# UART_LOGIC.net
KiCad netlist of a schematic drawn in Altium Designer
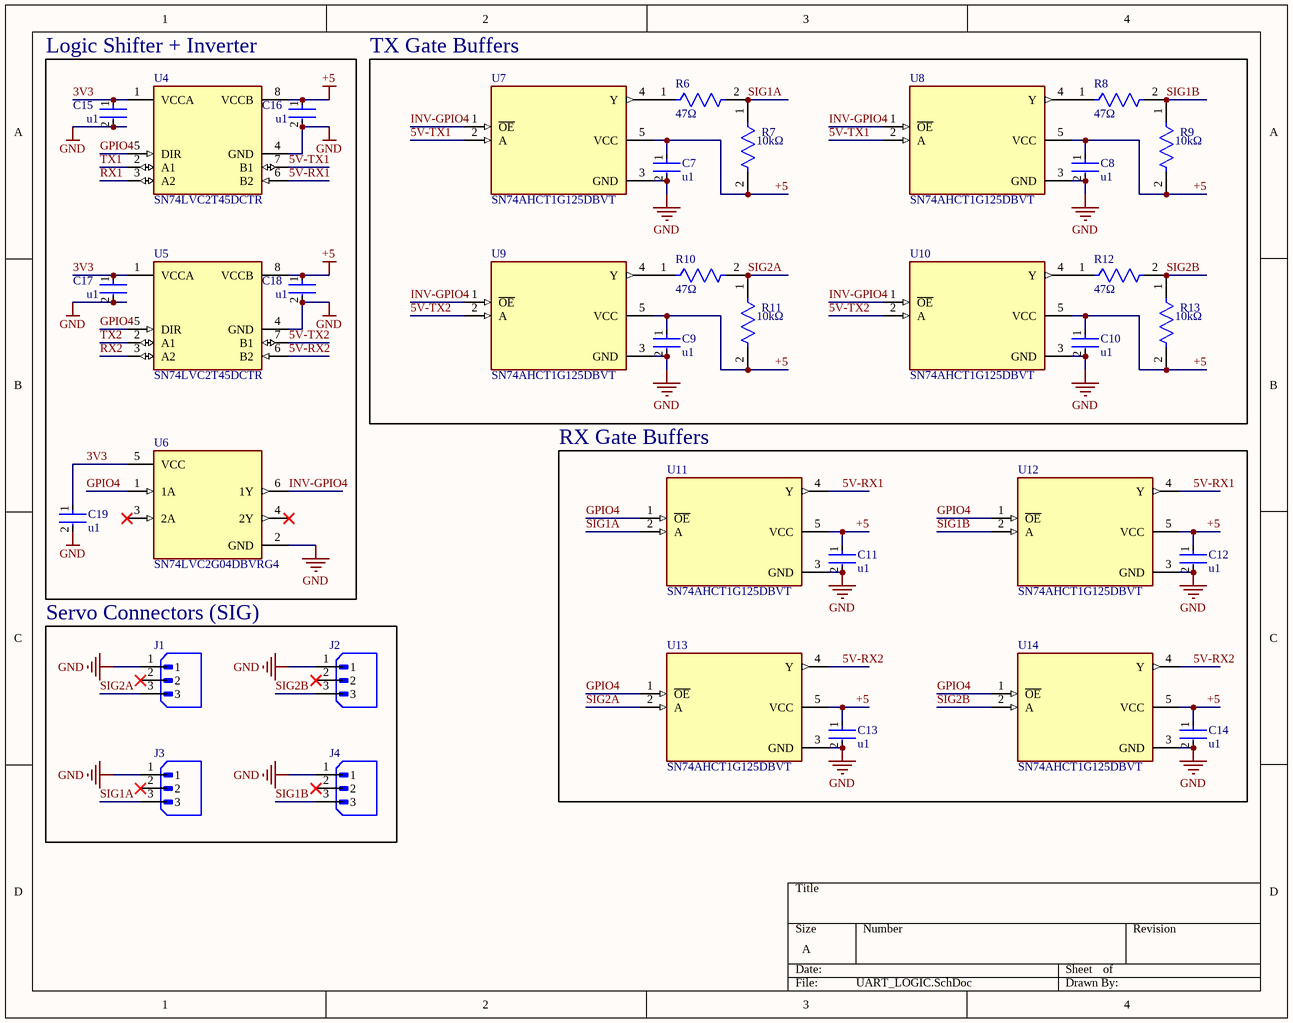
[diagram p0: UART_LOGIC.SchDoc]

(export (version "E")
  (design (tool "Eeschema 10.0.6"))
  (components
    (comp (ref "C7")
      (value "u1")
      (footprint "FP-CC0805-0_85-MFG")
      (description "CC0805KRX7R9BB104 CAP CER 0.1UF 50V X7R 0805")
      (fields (field (name "TOLERANCE") "0.1") (field (name "MANUFACTURER PART NUMBER") "CC0805KRX7R9BB104"))
      (libsource (lib "Altium Content Vault") (part "11868f565c42a9108669ba33697ecf6"))
    )
    (comp (ref "C8")
      (value "u1")
      (footprint "FP-CC0805-0_85-MFG")
      (description "CC0805KRX7R9BB104 CAP CER 0.1UF 50V X7R 0805")
      (fields (field (name "TOLERANCE") "0.1") (field (name "MANUFACTURER PART NUMBER") "CC0805KRX7R9BB104"))
      (libsource (lib "Altium Content Vault") (part "11868f565c42a9108669ba33697ecf6"))
    )
    (comp (ref "C9")
      (value "u1")
      (footprint "FP-CC0805-0_85-MFG")
      (description "CC0805KRX7R9BB104 CAP CER 0.1UF 50V X7R 0805")
      (fields (field (name "TOLERANCE") "0.1") (field (name "MANUFACTURER PART NUMBER") "CC0805KRX7R9BB104"))
      (libsource (lib "Altium Content Vault") (part "11868f565c42a9108669ba33697ecf6"))
    )
    (comp (ref "C10")
      (value "u1")
      (footprint "FP-CC0805-0_85-MFG")
      (description "CC0805KRX7R9BB104 CAP CER 0.1UF 50V X7R 0805")
      (fields (field (name "TOLERANCE") "0.1") (field (name "MANUFACTURER PART NUMBER") "CC0805KRX7R9BB104"))
      (libsource (lib "Altium Content Vault") (part "11868f565c42a9108669ba33697ecf6"))
    )
    (comp (ref "C11")
      (value "u1")
      (footprint "FP-CC0805-0_85-MFG")
      (description "CC0805KRX7R9BB104 CAP CER 0.1UF 50V X7R 0805")
      (fields (field (name "TOLERANCE") "0.1") (field (name "MANUFACTURER PART NUMBER") "CC0805KRX7R9BB104"))
      (libsource (lib "Altium Content Vault") (part "11868f565c42a9108669ba33697ecf6"))
    )
    (comp (ref "C12")
      (value "u1")
      (footprint "FP-CC0805-0_85-MFG")
      (description "CC0805KRX7R9BB104 CAP CER 0.1UF 50V X7R 0805")
      (fields (field (name "TOLERANCE") "0.1") (field (name "MANUFACTURER PART NUMBER") "CC0805KRX7R9BB104"))
      (libsource (lib "Altium Content Vault") (part "11868f565c42a9108669ba33697ecf6"))
    )
    (comp (ref "C13")
      (value "u1")
      (footprint "FP-CC0805-0_85-MFG")
      (description "CC0805KRX7R9BB104 CAP CER 0.1UF 50V X7R 0805")
      (fields (field (name "TOLERANCE") "0.1") (field (name "MANUFACTURER PART NUMBER") "CC0805KRX7R9BB104"))
      (libsource (lib "Altium Content Vault") (part "11868f565c42a9108669ba33697ecf6"))
    )
    (comp (ref "C14")
      (value "u1")
      (footprint "FP-CC0805-0_85-MFG")
      (description "CC0805KRX7R9BB104 CAP CER 0.1UF 50V X7R 0805")
      (fields (field (name "TOLERANCE") "0.1") (field (name "MANUFACTURER PART NUMBER") "CC0805KRX7R9BB104"))
      (libsource (lib "Altium Content Vault") (part "11868f565c42a9108669ba33697ecf6"))
    )
    (comp (ref "C15")
      (value "u1")
      (footprint "FP-CC0805-0_85-MFG")
      (description "CC0805KRX7R9BB104 CAP CER 0.1UF 50V X7R 0805")
      (fields (field (name "TOLERANCE") "0.1") (field (name "MANUFACTURER PART NUMBER") "CC0805KRX7R9BB104"))
      (libsource (lib "Altium Content Vault") (part "11868f565c42a9108669ba33697ecf6"))
    )
    (comp (ref "C16")
      (value "u1")
      (footprint "FP-CC0805-0_85-MFG")
      (description "CC0805KRX7R9BB104 CAP CER 0.1UF 50V X7R 0805")
      (fields (field (name "TOLERANCE") "0.1") (field (name "MANUFACTURER PART NUMBER") "CC0805KRX7R9BB104"))
      (libsource (lib "Altium Content Vault") (part "11868f565c42a9108669ba33697ecf6"))
    )
    (comp (ref "C17")
      (value "u1")
      (footprint "FP-CC0805-0_85-MFG")
      (description "CC0805KRX7R9BB104 CAP CER 0.1UF 50V X7R 0805")
      (fields (field (name "TOLERANCE") "0.1") (field (name "MANUFACTURER PART NUMBER") "CC0805KRX7R9BB104"))
      (libsource (lib "Altium Content Vault") (part "11868f565c42a9108669ba33697ecf6"))
    )
    (comp (ref "C18")
      (value "u1")
      (footprint "FP-CC0805-0_85-MFG")
      (description "CC0805KRX7R9BB104 CAP CER 0.1UF 50V X7R 0805")
      (fields (field (name "TOLERANCE") "0.1") (field (name "MANUFACTURER PART NUMBER") "CC0805KRX7R9BB104"))
      (libsource (lib "Altium Content Vault") (part "11868f565c42a9108669ba33697ecf6"))
    )
    (comp (ref "C19")
      (value "u1")
      (footprint "FP-CC0805-0_85-MFG")
      (description "CC0805KRX7R9BB104 CAP CER 0.1UF 50V X7R 0805")
      (fields (field (name "TOLERANCE") "0.1") (field (name "MANUFACTURER PART NUMBER") "CC0805KRX7R9BB104"))
      (libsource (lib "Altium Content Vault") (part "11868f565c42a9108669ba33697ecf6"))
    )
    (comp (ref "J1")
      (value "B3B-XH-A")
      (footprint "JST_B3B-XH-A")
      (description "Connector Header Through Hole 3 position 0.098 (2.50mm)")
      (fields (field (name "MF") "JST Sales"))
      (libsource (lib "Bryan Heddle") (part "B3B-XH-A"))
    )
    (comp (ref "J2")
      (value "B3B-XH-A")
      (footprint "JST_B3B-XH-A")
      (description "Connector Header Through Hole 3 position 0.098 (2.50mm)")
      (fields (field (name "MF") "JST Sales"))
      (libsource (lib "Bryan Heddle") (part "B3B-XH-A"))
    )
    (comp (ref "J3")
      (value "B3B-XH-A")
      (footprint "JST_B3B-XH-A")
      (description "Connector Header Through Hole 3 position 0.098 (2.50mm)")
      (fields (field (name "MF") "JST Sales"))
      (libsource (lib "Bryan Heddle") (part "B3B-XH-A"))
    )
    (comp (ref "J4")
      (value "B3B-XH-A")
      (footprint "JST_B3B-XH-A")
      (description "Connector Header Through Hole 3 position 0.098 (2.50mm)")
      (fields (field (name "MF") "JST Sales"))
      (libsource (lib "Bryan Heddle") (part "B3B-XH-A"))
    )
    (comp (ref "R6")
      (value "47Ω")
      (footprint "FP-RMCF0603-IPC_A")
      (description "47Ω ±1% 0.1W 0603 Thick Film Chip Resistor AEC-Q200 compliant RMCF0603FG47R0")
      (libsource (lib "Altium Content Vault") (part "1029c3af85768c4190bb7ad29bc67b5"))
    )
    (comp (ref "R7")
      (value "10kΩ")
      (footprint "FP-RMCF1206-MFG")
      (description "10kΩ ±1% 0.25W 1206 Thick Film Chip Resistor AEC-Q200 compliant RMCF1206FG10K0")
      (fields (field (name "TOLERANCE") "1%"))
      (libsource (lib "Altium Content Vault") (part "1029c3af85768c4190bb7ad29bc67b5"))
    )
    (comp (ref "R8")
      (value "47Ω")
      (footprint "FP-RMCF0603-IPC_A")
      (description "47Ω ±1% 0.1W 0603 Thick Film Chip Resistor AEC-Q200 compliant RMCF0603FG47R0")
      (libsource (lib "Altium Content Vault") (part "1029c3af85768c4190bb7ad29bc67b5"))
    )
    (comp (ref "R9")
      (value "10kΩ")
      (footprint "FP-RMCF1206-MFG")
      (description "10kΩ ±1% 0.25W 1206 Thick Film Chip Resistor AEC-Q200 compliant RMCF1206FG10K0")
      (fields (field (name "TOLERANCE") "1%"))
      (libsource (lib "Altium Content Vault") (part "1029c3af85768c4190bb7ad29bc67b5"))
    )
    (comp (ref "R10")
      (value "47Ω")
      (footprint "FP-RMCF0603-IPC_A")
      (description "47Ω ±1% 0.1W 0603 Thick Film Chip Resistor AEC-Q200 compliant RMCF0603FG47R0")
      (libsource (lib "Altium Content Vault") (part "1029c3af85768c4190bb7ad29bc67b5"))
    )
    (comp (ref "R11")
      (value "10kΩ")
      (footprint "FP-RMCF1206-MFG")
      (description "10kΩ ±1% 0.25W 1206 Thick Film Chip Resistor AEC-Q200 compliant RMCF1206FG10K0")
      (fields (field (name "TOLERANCE") "1%"))
      (libsource (lib "Altium Content Vault") (part "1029c3af85768c4190bb7ad29bc67b5"))
    )
    (comp (ref "R12")
      (value "47Ω")
      (footprint "FP-RMCF0603-IPC_A")
      (description "47Ω ±1% 0.1W 0603 Thick Film Chip Resistor AEC-Q200 compliant RMCF0603FG47R0")
      (libsource (lib "Altium Content Vault") (part "1029c3af85768c4190bb7ad29bc67b5"))
    )
    (comp (ref "R13")
      (value "10kΩ")
      (footprint "FP-RMCF1206-MFG")
      (description "10kΩ ±1% 0.25W 1206 Thick Film Chip Resistor AEC-Q200 compliant RMCF1206FG10K0")
      (fields (field (name "TOLERANCE") "1%"))
      (libsource (lib "Altium Content Vault") (part "1029c3af85768c4190bb7ad29bc67b5"))
    )
    (comp (ref "U4")
      (value "SN74LVC2T45DCTR")
      (footprint "FP-DCT0008A-IPC_C")
      (libsource (lib "Bryan Heddle") (part "271d40e9c72c712db4b2912206096bb"))
    )
    (comp (ref "U5")
      (value "SN74LVC2T45DCTR")
      (footprint "FP-DCT0008A-IPC_C")
      (libsource (lib "Bryan Heddle") (part "271d40e9c72c712db4b2912206096bb"))
    )
    (comp (ref "U6")
      (value "SN74LVC2G04DBVRG4")
      (footprint "FP-DBV0006A-MFG")
      (description "IC INVERTER 2CH 2-INP SOT23-6")
      (libsource (lib "Altium Content Vault") (part "9dfbf26b1eab2647ff4a890ff2a17ee"))
    )
    (comp (ref "U7")
      (value "SN74AHCT1G125DBVT")
      (footprint "SOT95P280X145-5N")
      (description "Single 4.5-V to 5.5-V buffer with TTL-compatible CMOS inputs and 3-state outputs")
      (fields (field (name "MF") "Texas Instruments"))
      (libsource (lib "Bryan Heddle") (part "SN74AHCT1G125DBVT"))
    )
    (comp (ref "U8")
      (value "SN74AHCT1G125DBVT")
      (footprint "SOT95P280X145-5N")
      (description "Single 4.5-V to 5.5-V buffer with TTL-compatible CMOS inputs and 3-state outputs")
      (fields (field (name "MF") "Texas Instruments"))
      (libsource (lib "Bryan Heddle") (part "SN74AHCT1G125DBVT"))
    )
    (comp (ref "U9")
      (value "SN74AHCT1G125DBVT")
      (footprint "SOT95P280X145-5N")
      (description "Single 4.5-V to 5.5-V buffer with TTL-compatible CMOS inputs and 3-state outputs")
      (fields (field (name "MF") "Texas Instruments"))
      (libsource (lib "Bryan Heddle") (part "SN74AHCT1G125DBVT"))
    )
    (comp (ref "U10")
      (value "SN74AHCT1G125DBVT")
      (footprint "SOT95P280X145-5N")
      (description "Single 4.5-V to 5.5-V buffer with TTL-compatible CMOS inputs and 3-state outputs")
      (fields (field (name "MF") "Texas Instruments"))
      (libsource (lib "Bryan Heddle") (part "SN74AHCT1G125DBVT"))
    )
    (comp (ref "U11")
      (value "SN74AHCT1G125DBVT")
      (footprint "SOT95P280X145-5N")
      (description "Single 4.5-V to 5.5-V buffer with TTL-compatible CMOS inputs and 3-state outputs")
      (fields (field (name "MF") "Texas Instruments"))
      (libsource (lib "Bryan Heddle") (part "SN74AHCT1G125DBVT"))
    )
    (comp (ref "U12")
      (value "SN74AHCT1G125DBVT")
      (footprint "SOT95P280X145-5N")
      (description "Single 4.5-V to 5.5-V buffer with TTL-compatible CMOS inputs and 3-state outputs")
      (fields (field (name "MF") "Texas Instruments"))
      (libsource (lib "Bryan Heddle") (part "SN74AHCT1G125DBVT"))
    )
    (comp (ref "U13")
      (value "SN74AHCT1G125DBVT")
      (footprint "SOT95P280X145-5N")
      (description "Single 4.5-V to 5.5-V buffer with TTL-compatible CMOS inputs and 3-state outputs")
      (fields (field (name "MF") "Texas Instruments"))
      (libsource (lib "Bryan Heddle") (part "SN74AHCT1G125DBVT"))
    )
    (comp (ref "U14")
      (value "SN74AHCT1G125DBVT")
      (footprint "SOT95P280X145-5N")
      (description "Single 4.5-V to 5.5-V buffer with TTL-compatible CMOS inputs and 3-state outputs")
      (fields (field (name "MF") "Texas Instruments"))
      (libsource (lib "Bryan Heddle") (part "SN74AHCT1G125DBVT"))
    )
  )
  (nets
    (net (code "1") (name "+5") (class "Default")
      (node (ref "C10") (pin "1") (pinfunction "1_1") (pintype "passive"))
      (node (ref "C11") (pin "1") (pinfunction "1_1") (pintype "passive"))
      (node (ref "C12") (pin "1") (pinfunction "1_1") (pintype "passive"))
      (node (ref "C13") (pin "1") (pinfunction "1_1") (pintype "passive"))
      (node (ref "C14") (pin "1") (pinfunction "1_1") (pintype "passive"))
      (node (ref "C16") (pin "1") (pinfunction "1_1") (pintype "passive"))
      (node (ref "C18") (pin "1") (pinfunction "1_1") (pintype "passive"))
      (node (ref "C7") (pin "1") (pinfunction "1_1") (pintype "passive"))
      (node (ref "C8") (pin "1") (pinfunction "1_1") (pintype "passive"))
      (node (ref "C9") (pin "1") (pinfunction "1_1") (pintype "passive"))
      (node (ref "R11") (pin "2") (pinfunction "2_2") (pintype "passive"))
      (node (ref "R13") (pin "2") (pinfunction "2_2") (pintype "passive"))
      (node (ref "R7") (pin "2") (pinfunction "2_2") (pintype "passive"))
      (node (ref "R9") (pin "2") (pinfunction "2_2") (pintype "passive"))
      (node (ref "U10") (pin "5") (pinfunction "VCC_5") (pintype "power_in"))
      (node (ref "U11") (pin "5") (pinfunction "VCC_5") (pintype "power_in"))
      (node (ref "U12") (pin "5") (pinfunction "VCC_5") (pintype "power_in"))
      (node (ref "U13") (pin "5") (pinfunction "VCC_5") (pintype "power_in"))
      (node (ref "U14") (pin "5") (pinfunction "VCC_5") (pintype "power_in"))
      (node (ref "U4") (pin "8") (pinfunction "VCCB_8") (pintype "power_in"))
      (node (ref "U5") (pin "8") (pinfunction "VCCB_8") (pintype "power_in"))
      (node (ref "U7") (pin "5") (pinfunction "VCC_5") (pintype "power_in"))
      (node (ref "U8") (pin "5") (pinfunction "VCC_5") (pintype "power_in"))
      (node (ref "U9") (pin "5") (pinfunction "VCC_5") (pintype "power_in"))
    )
    (net (code "2") (name "/3V3") (class "Default")
      (node (ref "C15") (pin "1") (pinfunction "1_1") (pintype "passive"))
      (node (ref "C17") (pin "1") (pinfunction "1_1") (pintype "passive"))
      (node (ref "C19") (pin "1") (pinfunction "1_1") (pintype "passive"))
      (node (ref "U4") (pin "1") (pinfunction "VCCA_1") (pintype "power_in"))
      (node (ref "U5") (pin "1") (pinfunction "VCCA_1") (pintype "power_in"))
      (node (ref "U6") (pin "5") (pinfunction "VCC_5") (pintype "power_in"))
    )
    (net (code "3") (name "/5V-RX1") (class "Default")
      (node (ref "U11") (pin "4") (pinfunction "Y_4") (pintype "output"))
      (node (ref "U12") (pin "4") (pinfunction "Y_4") (pintype "output"))
      (node (ref "U4") (pin "6") (pinfunction "B2_6") (pintype "input"))
    )
    (net (code "4") (name "/5V-RX2") (class "Default")
      (node (ref "U13") (pin "4") (pinfunction "Y_4") (pintype "output"))
      (node (ref "U14") (pin "4") (pinfunction "Y_4") (pintype "output"))
      (node (ref "U5") (pin "6") (pinfunction "B2_6") (pintype "input"))
    )
    (net (code "5") (name "/5V-TX1") (class "Default")
      (node (ref "U4") (pin "7") (pinfunction "B1_7") (pintype "bidirectional"))
      (node (ref "U7") (pin "2") (pinfunction "A_2") (pintype "input"))
      (node (ref "U8") (pin "2") (pinfunction "A_2") (pintype "input"))
    )
    (net (code "6") (name "/5V-TX2") (class "Default")
      (node (ref "U10") (pin "2") (pinfunction "A_2") (pintype "input"))
      (node (ref "U5") (pin "7") (pinfunction "B1_7") (pintype "bidirectional"))
      (node (ref "U9") (pin "2") (pinfunction "A_2") (pintype "input"))
    )
    (net (code "7") (name "/GPIO4") (class "Default")
      (node (ref "U11") (pin "1") (pinfunction "~{OE}_1") (pintype "input"))
      (node (ref "U12") (pin "1") (pinfunction "~{OE}_1") (pintype "input"))
      (node (ref "U13") (pin "1") (pinfunction "~{OE}_1") (pintype "input"))
      (node (ref "U14") (pin "1") (pinfunction "~{OE}_1") (pintype "input"))
      (node (ref "U4") (pin "5") (pinfunction "DIR_5") (pintype "input"))
      (node (ref "U5") (pin "5") (pinfunction "DIR_5") (pintype "input"))
      (node (ref "U6") (pin "1") (pinfunction "1A_1") (pintype "input"))
    )
    (net (code "8") (name "/INV-GPIO4") (class "Default")
      (node (ref "U10") (pin "1") (pinfunction "~{OE}_1") (pintype "input"))
      (node (ref "U6") (pin "6") (pinfunction "1Y_6") (pintype "output"))
      (node (ref "U7") (pin "1") (pinfunction "~{OE}_1") (pintype "input"))
      (node (ref "U8") (pin "1") (pinfunction "~{OE}_1") (pintype "input"))
      (node (ref "U9") (pin "1") (pinfunction "~{OE}_1") (pintype "input"))
    )
    (net (code "9") (name "/RX1") (class "Default")
      (node (ref "U4") (pin "3") (pinfunction "A2_3") (pintype "bidirectional"))
    )
    (net (code "10") (name "/RX2") (class "Default")
      (node (ref "U5") (pin "3") (pinfunction "A2_3") (pintype "bidirectional"))
    )
    (net (code "11") (name "/SIG1A") (class "Default")
      (node (ref "J3") (pin "3") (pinfunction "3_3") (pintype "passive"))
      (node (ref "R6") (pin "2") (pinfunction "2_2") (pintype "passive"))
      (node (ref "R7") (pin "1") (pinfunction "1_1") (pintype "passive"))
      (node (ref "U11") (pin "2") (pinfunction "A_2") (pintype "input"))
    )
    (net (code "12") (name "/SIG1B") (class "Default")
      (node (ref "J4") (pin "3") (pinfunction "3_3") (pintype "passive"))
      (node (ref "R8") (pin "2") (pinfunction "2_2") (pintype "passive"))
      (node (ref "R9") (pin "1") (pinfunction "1_1") (pintype "passive"))
      (node (ref "U12") (pin "2") (pinfunction "A_2") (pintype "input"))
    )
    (net (code "13") (name "/SIG2A") (class "Default")
      (node (ref "J1") (pin "3") (pinfunction "3_3") (pintype "passive"))
      (node (ref "R10") (pin "2") (pinfunction "2_2") (pintype "passive"))
      (node (ref "R11") (pin "1") (pinfunction "1_1") (pintype "passive"))
      (node (ref "U13") (pin "2") (pinfunction "A_2") (pintype "input"))
    )
    (net (code "14") (name "/SIG2B") (class "Default")
      (node (ref "J2") (pin "3") (pinfunction "3_3") (pintype "passive"))
      (node (ref "R12") (pin "2") (pinfunction "2_2") (pintype "passive"))
      (node (ref "R13") (pin "1") (pinfunction "1_1") (pintype "passive"))
      (node (ref "U14") (pin "2") (pinfunction "A_2") (pintype "input"))
    )
    (net (code "15") (name "/TX1") (class "Default")
      (node (ref "U4") (pin "2") (pinfunction "A1_2") (pintype "bidirectional"))
    )
    (net (code "16") (name "/TX2") (class "Default")
      (node (ref "U5") (pin "2") (pinfunction "A1_2") (pintype "bidirectional"))
    )
    (net (code "17") (name "GND") (class "Default")
      (node (ref "C10") (pin "2") (pinfunction "2_2") (pintype "passive"))
      (node (ref "C11") (pin "2") (pinfunction "2_2") (pintype "passive"))
      (node (ref "C12") (pin "2") (pinfunction "2_2") (pintype "passive"))
      (node (ref "C13") (pin "2") (pinfunction "2_2") (pintype "passive"))
      (node (ref "C14") (pin "2") (pinfunction "2_2") (pintype "passive"))
      (node (ref "C15") (pin "2") (pinfunction "2_2") (pintype "passive"))
      (node (ref "C16") (pin "2") (pinfunction "2_2") (pintype "passive"))
      (node (ref "C17") (pin "2") (pinfunction "2_2") (pintype "passive"))
      (node (ref "C18") (pin "2") (pinfunction "2_2") (pintype "passive"))
      (node (ref "C19") (pin "2") (pinfunction "2_2") (pintype "passive"))
      (node (ref "C7") (pin "2") (pinfunction "2_2") (pintype "passive"))
      (node (ref "C8") (pin "2") (pinfunction "2_2") (pintype "passive"))
      (node (ref "C9") (pin "2") (pinfunction "2_2") (pintype "passive"))
      (node (ref "J1") (pin "1") (pinfunction "1_1") (pintype "passive"))
      (node (ref "J2") (pin "1") (pinfunction "1_1") (pintype "passive"))
      (node (ref "J3") (pin "1") (pinfunction "1_1") (pintype "passive"))
      (node (ref "J4") (pin "1") (pinfunction "1_1") (pintype "passive"))
      (node (ref "U10") (pin "3") (pinfunction "GND_3") (pintype "power_in"))
      (node (ref "U11") (pin "3") (pinfunction "GND_3") (pintype "power_in"))
      (node (ref "U12") (pin "3") (pinfunction "GND_3") (pintype "power_in"))
      (node (ref "U13") (pin "3") (pinfunction "GND_3") (pintype "power_in"))
      (node (ref "U14") (pin "3") (pinfunction "GND_3") (pintype "power_in"))
      (node (ref "U4") (pin "4") (pinfunction "GND_4") (pintype "power_in"))
      (node (ref "U5") (pin "4") (pinfunction "GND_4") (pintype "power_in"))
      (node (ref "U6") (pin "2") (pinfunction "GND_2") (pintype "power_in"))
      (node (ref "U7") (pin "3") (pinfunction "GND_3") (pintype "power_in"))
      (node (ref "U8") (pin "3") (pinfunction "GND_3") (pintype "power_in"))
      (node (ref "U9") (pin "3") (pinfunction "GND_3") (pintype "power_in"))
    )
    (net (code "18") (name "Net-(U7-Y)") (class "Default")
      (node (ref "R6") (pin "1") (pinfunction "1_1") (pintype "passive"))
      (node (ref "U7") (pin "4") (pinfunction "Y_4") (pintype "output"))
    )
    (net (code "19") (name "Net-(U8-Y)") (class "Default")
      (node (ref "R8") (pin "1") (pinfunction "1_1") (pintype "passive"))
      (node (ref "U8") (pin "4") (pinfunction "Y_4") (pintype "output"))
    )
    (net (code "20") (name "Net-(U9-Y)") (class "Default")
      (node (ref "R10") (pin "1") (pinfunction "1_1") (pintype "passive"))
      (node (ref "U9") (pin "4") (pinfunction "Y_4") (pintype "output"))
    )
    (net (code "21") (name "Net-(U10-Y)") (class "Default")
      (node (ref "R12") (pin "1") (pinfunction "1_1") (pintype "passive"))
      (node (ref "U10") (pin "4") (pinfunction "Y_4") (pintype "output"))
    )
    (net (code "22") (name "unconnected-(J1-Pad2)") (class "Default")
      (node (ref "J1") (pin "2") (pinfunction "2_2") (pintype "passive+no_connect"))
    )
    (net (code "23") (name "unconnected-(J2-Pad2)") (class "Default")
      (node (ref "J2") (pin "2") (pinfunction "2_2") (pintype "passive+no_connect"))
    )
    (net (code "24") (name "unconnected-(J3-Pad2)") (class "Default")
      (node (ref "J3") (pin "2") (pinfunction "2_2") (pintype "passive+no_connect"))
    )
    (net (code "25") (name "unconnected-(J4-Pad2)") (class "Default")
      (node (ref "J4") (pin "2") (pinfunction "2_2") (pintype "passive+no_connect"))
    )
    (net (code "26") (name "unconnected-(U6-2A-Pad3)") (class "Default")
      (node (ref "U6") (pin "3") (pinfunction "2A_3") (pintype "input+no_connect"))
    )
    (net (code "27") (name "unconnected-(U6-2Y-Pad4)") (class "Default")
      (node (ref "U6") (pin "4") (pinfunction "2Y_4") (pintype "output+no_connect"))
    )
  )
)
